# UPS.net
KiCad netlist of a schematic drawn in Altium Designer
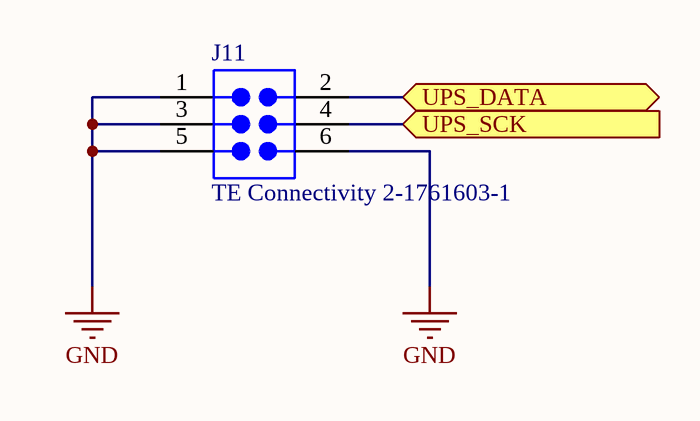
[diagram p0: UPS.SchDoc]

(export (version "E")
  (design (tool "Eeschema 10.0.6"))
  (components
    (comp (ref "J11")
      (value "TE Connectivity 2-1761603-1")
      (footprint "PCB-alggvk0m4hnepl8fg6xg-1")
      (description "Wire-To-Board Connector, AMP-LATCH Series, Through Hole, Header, 6, 2.54 mm, Gold Plated Contacts")
      (libsource (lib "CommunityVault") (part "SYM-78cdb343a32fa70a-1"))
    )
  )
  (nets
    (net (code "1") (name "/UPS_DATA") (class "Default")
      (node (ref "J11") (pin "2") (pinfunction "2_2") (pintype "passive"))
    )
    (net (code "2") (name "/UPS_SCK") (class "Default")
      (node (ref "J11") (pin "4") (pinfunction "4_4") (pintype "passive"))
    )
    (net (code "3") (name "GND") (class "Default")
      (node (ref "J11") (pin "1") (pinfunction "1_1") (pintype "passive"))
      (node (ref "J11") (pin "3") (pinfunction "3_3") (pintype "passive"))
      (node (ref "J11") (pin "5") (pinfunction "5_5") (pintype "passive"))
      (node (ref "J11") (pin "6") (pinfunction "6_6") (pintype "passive"))
    )
  )
)
